# WiFi_Card.net
KiCad netlist of a schematic drawn in Altium Designer
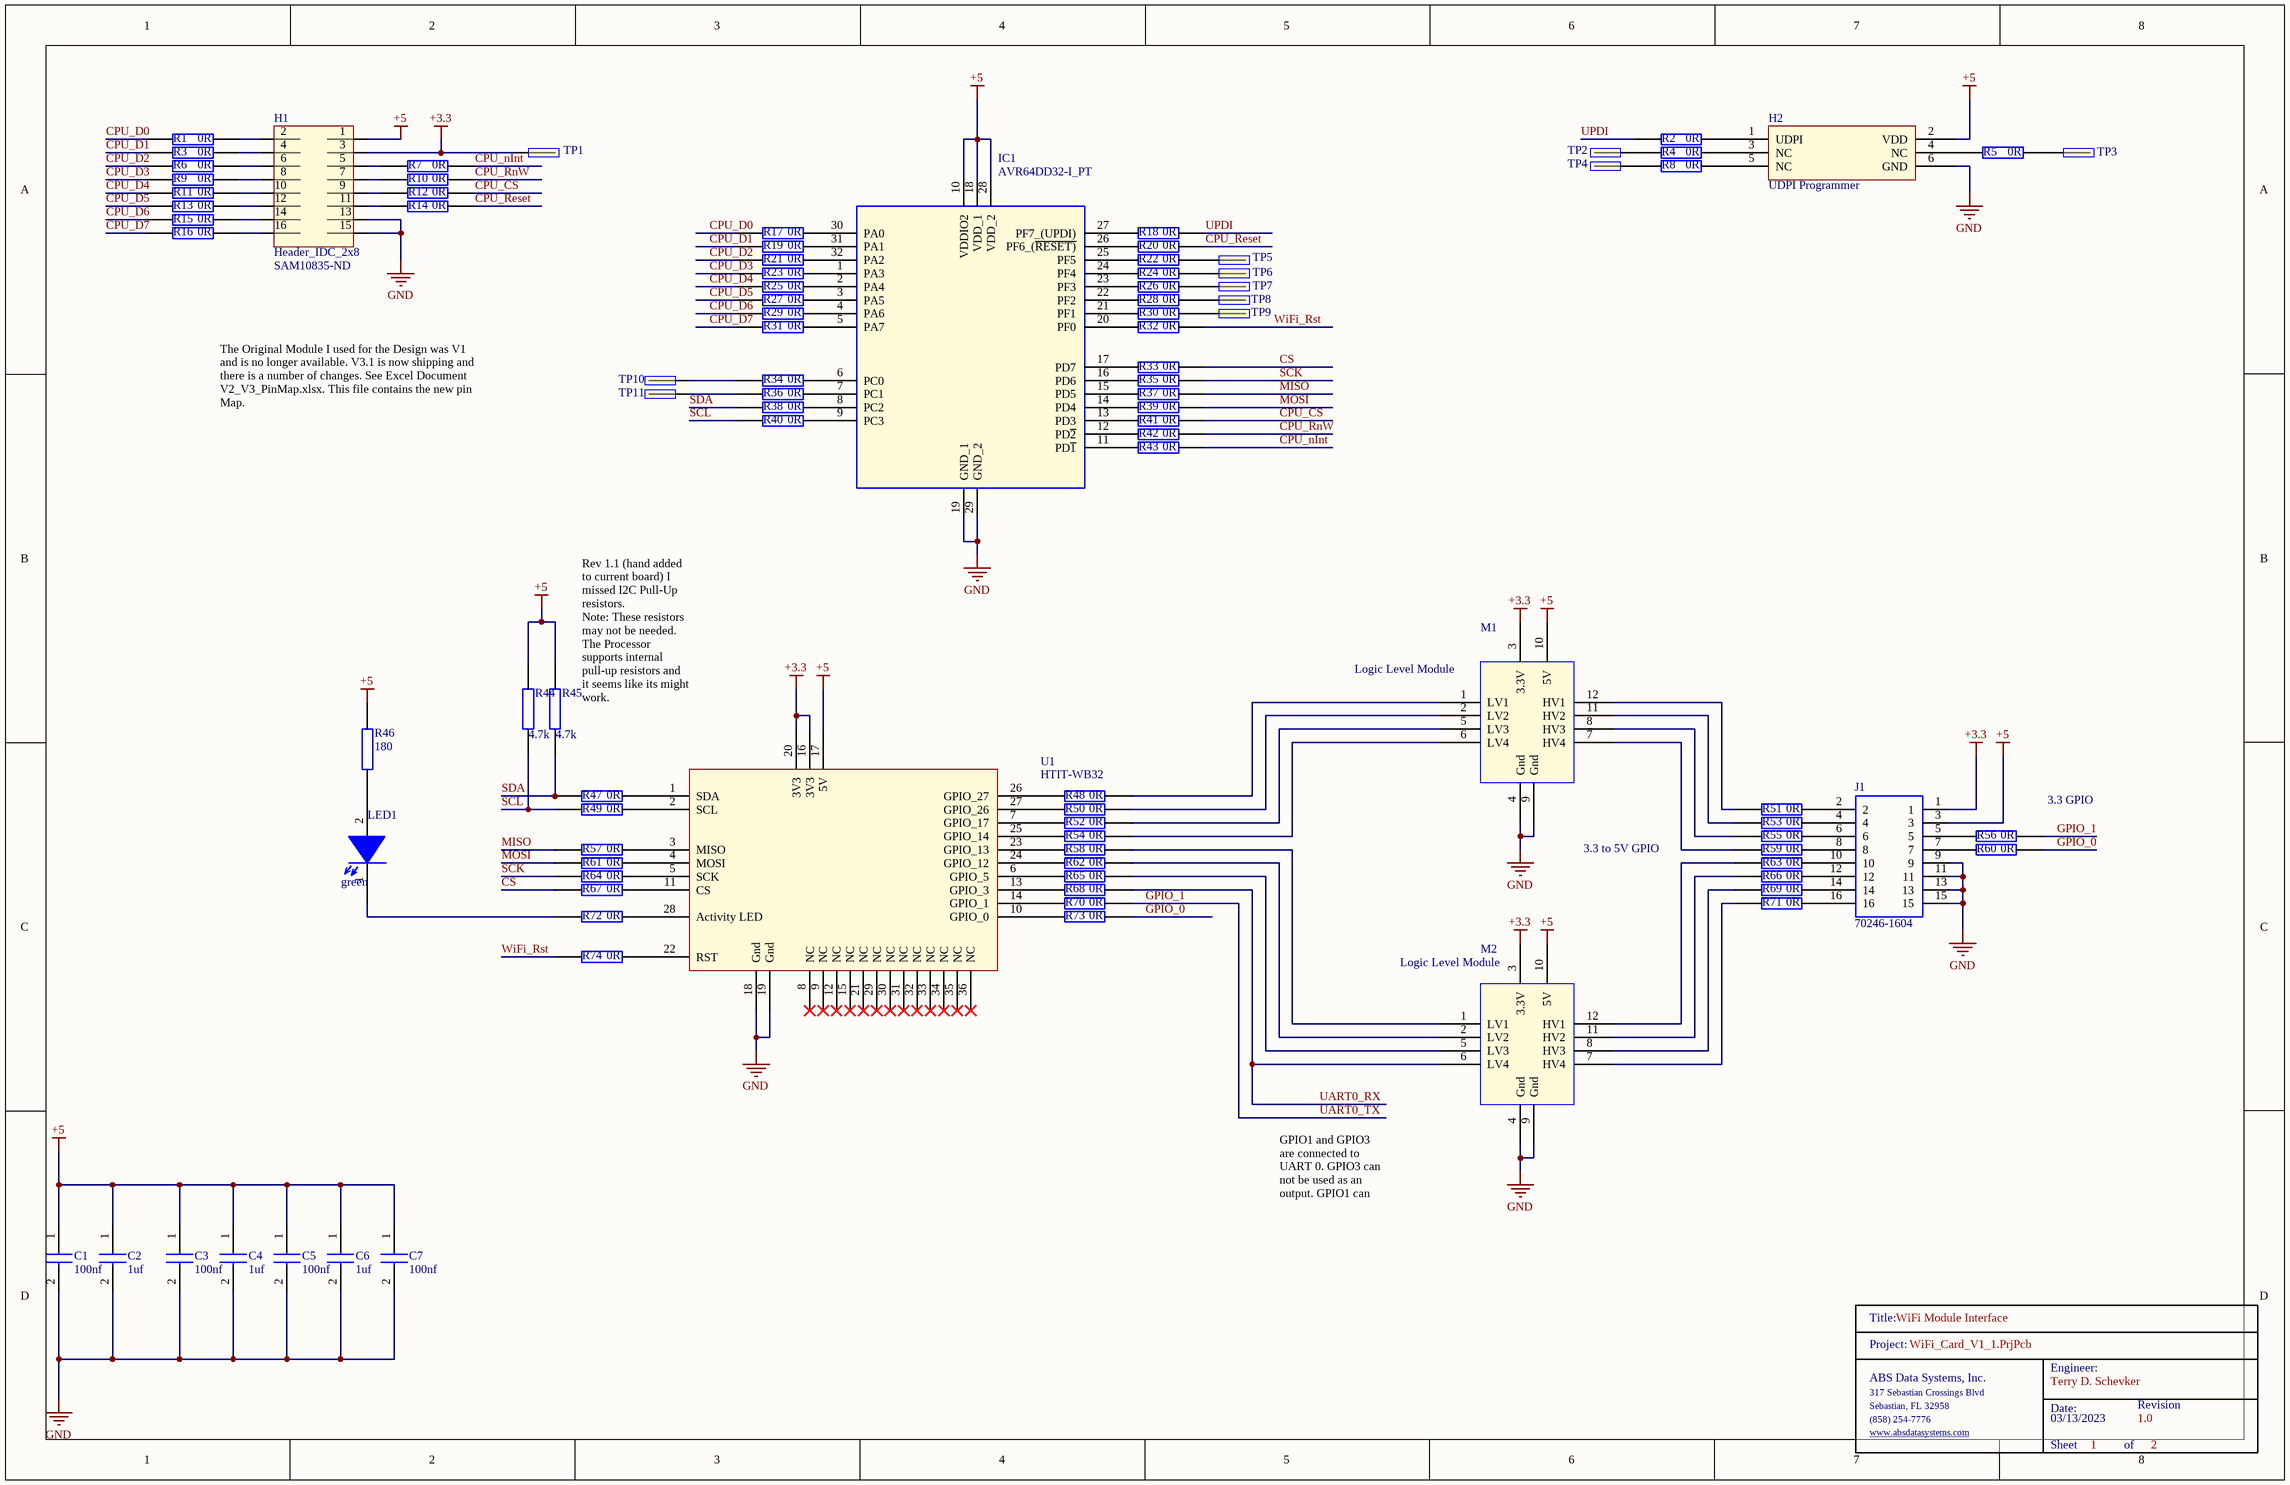
[diagram p0: WiFi_Card.SchDoc]

(export (version "E")
  (design (tool "Eeschema 10.0.6"))
  (components
    (comp (ref "C1")
      (value "100nf")
      (footprint "0603")
      (description "Samsung Electro-Mechanics 0603 100nf")
      (libsource (lib "Capacitors") (part "CL10B104JB8NNNC"))
    )
    (comp (ref "C2")
      (value "1uf")
      (footprint "0603")
      (description "Samsung Electro-Mechanics 0603 1uf")
      (libsource (lib "Capacitors") (part "CL10B105KA8NNNL"))
    )
    (comp (ref "C3")
      (value "100nf")
      (footprint "0603")
      (description "Samsung Electro-Mechanics 0603 100nf")
      (libsource (lib "Capacitors") (part "CL10B104JB8NNNC"))
    )
    (comp (ref "C4")
      (value "1uf")
      (footprint "0603")
      (description "Samsung Electro-Mechanics 0603 1uf")
      (libsource (lib "Capacitors") (part "CL10B105KA8NNNL"))
    )
    (comp (ref "C5")
      (value "100nf")
      (footprint "0603")
      (description "Samsung Electro-Mechanics 0603 100nf")
      (libsource (lib "Capacitors") (part "CL10B104JB8NNNC"))
    )
    (comp (ref "C6")
      (value "1uf")
      (footprint "0603")
      (description "Samsung Electro-Mechanics 0603 1uf")
      (libsource (lib "Capacitors") (part "CL10B105KA8NNNL"))
    )
    (comp (ref "C7")
      (value "100nf")
      (footprint "0603")
      (description "Samsung Electro-Mechanics 0603 100nf")
      (libsource (lib "Capacitors") (part "CL10B104JB8NNNC"))
    )
    (comp (ref "H1")
      (value "Header_IDC_2x8")
      (footprint "HEADER16")
      (description "16 Pin 2x8 Through Hold IDC Connector")
      (fields
        (field (name "MANUFACTURER") "Samtec")
        (field (name "MANUFACTURER PART NUMBER") "TST-108-01-G-D")
        (field (name "SUPPLIER PART NUMBER 1") "SAM10835-ND")
      )
      (libsource (lib "Misc") (part "Header_IDC_2x8"))
    )
    (comp (ref "H2")
      (value "UDPI Programmer")
      (footprint "HDR2X3")
      (description "6 Pin 2X3 Through Hole Header")
      (libsource (lib "Misc") (part "UDPI Programmer"))
    )
    (comp (ref "IC1")
      (value "AVR64DD32-I_PT")
      (footprint "CPU_Memory:QFP80P900X900X120-32N")
      (description "Integrated Circuit")
      (fields (field (name "MANUFACTURER_PART_NUMBER") "AVR64DD32-I/PT ¦ MULTI-VOLTAGE I/O"))
      (libsource (lib "CPU_Memory") (part "AVR64DD32-I_PT"))
    )
    (comp (ref "J1")
      (value "70246-1604")
      (footprint "SHDR16W99P254_2X8_2794X889X927P")
      (description "Molex C-GRID 70246, 2.54mm Pitch, 16 Way, 2 Row, Straight PCB Header, Through Hole")
      (fields (field (name "MOUSER PART NUMBER") "538-70246-1604"))
      (libsource (lib "Connectors") (part "70246-1604"))
    )
    (comp (ref "LED1")
      (value "green")
      (footprint "0603_Diode")
      (description "Wurth Elektronik 0603 green")
      (fields
        (field (name "MANUFACTURER") "Wurth Electronics")
        (field (name "MANUFACTURER PART NUMBER") "150060GS75000")
      )
      (libsource (lib "Misc") (part "150060GS75000"))
    )
    (comp (ref "M1")
      (value "Logic Level Module")
      (footprint "Logic_Level_Module")
      (description "Logic Level Converter Module")
      (libsource (lib "Logic") (part "Logic_Level_Module"))
    )
    (comp (ref "M2")
      (value "Logic Level Module")
      (footprint "Logic_Level_Module")
      (description "Logic Level Converter Module")
      (libsource (lib "Logic") (part "Logic_Level_Module"))
    )
    (comp (ref "R1")
      (value "0R")
      (footprint "0603")
      (description "YAGEO 0603 0 ohm")
      (fields
        (field (name "MOUSER PART NUMBER") "603-RC0603JR-070RL")
        (field (name "MANUFACTURER_PART_NUMBER") "RC0603JR-070RL")
      )
      (libsource (lib "Resistors") (part "RC0603JR-070RL"))
    )
    (comp (ref "R2")
      (value "0R")
      (footprint "0603")
      (description "YAGEO 0603 0 ohm")
      (fields
        (field (name "MOUSER PART NUMBER") "603-RC0603JR-070RL")
        (field (name "MANUFACTURER_PART_NUMBER") "RC0603JR-070RL")
      )
      (libsource (lib "Resistors") (part "RC0603JR-070RL"))
    )
    (comp (ref "R3")
      (value "0R")
      (footprint "0603")
      (description "YAGEO 0603 0 ohm")
      (fields
        (field (name "MOUSER PART NUMBER") "603-RC0603JR-070RL")
        (field (name "MANUFACTURER_PART_NUMBER") "RC0603JR-070RL")
      )
      (libsource (lib "Resistors") (part "RC0603JR-070RL"))
    )
    (comp (ref "R4")
      (value "0R")
      (footprint "0603")
      (description "YAGEO 0603 0 ohm")
      (fields
        (field (name "MOUSER PART NUMBER") "603-RC0603JR-070RL")
        (field (name "MANUFACTURER_PART_NUMBER") "RC0603JR-070RL")
      )
      (libsource (lib "Resistors") (part "RC0603JR-070RL"))
    )
    (comp (ref "R5")
      (value "0R")
      (footprint "0603")
      (description "YAGEO 0603 0 ohm")
      (fields
        (field (name "MOUSER PART NUMBER") "603-RC0603JR-070RL")
        (field (name "MANUFACTURER_PART_NUMBER") "RC0603JR-070RL")
      )
      (libsource (lib "Resistors") (part "RC0603JR-070RL"))
    )
    (comp (ref "R6")
      (value "0R")
      (footprint "0603")
      (description "YAGEO 0603 0 ohm")
      (fields
        (field (name "MOUSER PART NUMBER") "603-RC0603JR-070RL")
        (field (name "MANUFACTURER_PART_NUMBER") "RC0603JR-070RL")
      )
      (libsource (lib "Resistors") (part "RC0603JR-070RL"))
    )
    (comp (ref "R7")
      (value "0R")
      (footprint "0603")
      (description "YAGEO 0603 0 ohm")
      (fields
        (field (name "MOUSER PART NUMBER") "603-RC0603JR-070RL")
        (field (name "MANUFACTURER_PART_NUMBER") "RC0603JR-070RL")
      )
      (libsource (lib "Resistors") (part "RC0603JR-070RL"))
    )
    (comp (ref "R8")
      (value "0R")
      (footprint "0603")
      (description "YAGEO 0603 0 ohm")
      (fields
        (field (name "MOUSER PART NUMBER") "603-RC0603JR-070RL")
        (field (name "MANUFACTURER_PART_NUMBER") "RC0603JR-070RL")
      )
      (libsource (lib "Resistors") (part "RC0603JR-070RL"))
    )
    (comp (ref "R9")
      (value "0R")
      (footprint "0603")
      (description "YAGEO 0603 0 ohm")
      (fields
        (field (name "MOUSER PART NUMBER") "603-RC0603JR-070RL")
        (field (name "MANUFACTURER_PART_NUMBER") "RC0603JR-070RL")
      )
      (libsource (lib "Resistors") (part "RC0603JR-070RL"))
    )
    (comp (ref "R10")
      (value "0R")
      (footprint "0603")
      (description "YAGEO 0603 0 ohm")
      (fields
        (field (name "MOUSER PART NUMBER") "603-RC0603JR-070RL")
        (field (name "MANUFACTURER_PART_NUMBER") "RC0603JR-070RL")
      )
      (libsource (lib "Resistors") (part "RC0603JR-070RL"))
    )
    (comp (ref "R11")
      (value "0R")
      (footprint "0603")
      (description "YAGEO 0603 0 ohm")
      (fields
        (field (name "MOUSER PART NUMBER") "603-RC0603JR-070RL")
        (field (name "MANUFACTURER_PART_NUMBER") "RC0603JR-070RL")
      )
      (libsource (lib "Resistors") (part "RC0603JR-070RL"))
    )
    (comp (ref "R12")
      (value "0R")
      (footprint "0603")
      (description "YAGEO 0603 0 ohm")
      (fields
        (field (name "MOUSER PART NUMBER") "603-RC0603JR-070RL")
        (field (name "MANUFACTURER_PART_NUMBER") "RC0603JR-070RL")
      )
      (libsource (lib "Resistors") (part "RC0603JR-070RL"))
    )
    (comp (ref "R13")
      (value "0R")
      (footprint "0603")
      (description "YAGEO 0603 0 ohm")
      (fields
        (field (name "MOUSER PART NUMBER") "603-RC0603JR-070RL")
        (field (name "MANUFACTURER_PART_NUMBER") "RC0603JR-070RL")
      )
      (libsource (lib "Resistors") (part "RC0603JR-070RL"))
    )
    (comp (ref "R14")
      (value "0R")
      (footprint "0603")
      (description "YAGEO 0603 0 ohm")
      (fields
        (field (name "MOUSER PART NUMBER") "603-RC0603JR-070RL")
        (field (name "MANUFACTURER_PART_NUMBER") "RC0603JR-070RL")
      )
      (libsource (lib "Resistors") (part "RC0603JR-070RL"))
    )
    (comp (ref "R15")
      (value "0R")
      (footprint "0603")
      (description "YAGEO 0603 0 ohm")
      (fields
        (field (name "MOUSER PART NUMBER") "603-RC0603JR-070RL")
        (field (name "MANUFACTURER_PART_NUMBER") "RC0603JR-070RL")
      )
      (libsource (lib "Resistors") (part "RC0603JR-070RL"))
    )
    (comp (ref "R16")
      (value "0R")
      (footprint "0603")
      (description "YAGEO 0603 0 ohm")
      (fields
        (field (name "MOUSER PART NUMBER") "603-RC0603JR-070RL")
        (field (name "MANUFACTURER_PART_NUMBER") "RC0603JR-070RL")
      )
      (libsource (lib "Resistors") (part "RC0603JR-070RL"))
    )
    (comp (ref "R17")
      (value "0R")
      (footprint "0603")
      (description "YAGEO 0603 0 ohm")
      (fields
        (field (name "MOUSER PART NUMBER") "603-RC0603JR-070RL")
        (field (name "MANUFACTURER_PART_NUMBER") "RC0603JR-070RL")
      )
      (libsource (lib "Resistors") (part "RC0603JR-070RL"))
    )
    (comp (ref "R18")
      (value "0R")
      (footprint "0603")
      (description "YAGEO 0603 0 ohm")
      (fields
        (field (name "MOUSER PART NUMBER") "603-RC0603JR-070RL")
        (field (name "MANUFACTURER_PART_NUMBER") "RC0603JR-070RL")
      )
      (libsource (lib "Resistors") (part "RC0603JR-070RL"))
    )
    (comp (ref "R19")
      (value "0R")
      (footprint "0603")
      (description "YAGEO 0603 0 ohm")
      (fields
        (field (name "MOUSER PART NUMBER") "603-RC0603JR-070RL")
        (field (name "MANUFACTURER_PART_NUMBER") "RC0603JR-070RL")
      )
      (libsource (lib "Resistors") (part "RC0603JR-070RL"))
    )
    (comp (ref "R20")
      (value "0R")
      (footprint "0603")
      (description "YAGEO 0603 0 ohm")
      (fields
        (field (name "MOUSER PART NUMBER") "603-RC0603JR-070RL")
        (field (name "MANUFACTURER_PART_NUMBER") "RC0603JR-070RL")
      )
      (libsource (lib "Resistors") (part "RC0603JR-070RL"))
    )
    (comp (ref "R21")
      (value "0R")
      (footprint "0603")
      (description "YAGEO 0603 0 ohm")
      (fields
        (field (name "MOUSER PART NUMBER") "603-RC0603JR-070RL")
        (field (name "MANUFACTURER_PART_NUMBER") "RC0603JR-070RL")
      )
      (libsource (lib "Resistors") (part "RC0603JR-070RL"))
    )
    (comp (ref "R22")
      (value "0R")
      (footprint "0603")
      (description "YAGEO 0603 0 ohm")
      (fields
        (field (name "MOUSER PART NUMBER") "603-RC0603JR-070RL")
        (field (name "MANUFACTURER_PART_NUMBER") "RC0603JR-070RL")
      )
      (libsource (lib "Resistors") (part "RC0603JR-070RL"))
    )
    (comp (ref "R23")
      (value "0R")
      (footprint "0603")
      (description "YAGEO 0603 0 ohm")
      (fields
        (field (name "MOUSER PART NUMBER") "603-RC0603JR-070RL")
        (field (name "MANUFACTURER_PART_NUMBER") "RC0603JR-070RL")
      )
      (libsource (lib "Resistors") (part "RC0603JR-070RL"))
    )
    (comp (ref "R24")
      (value "0R")
      (footprint "0603")
      (description "YAGEO 0603 0 ohm")
      (fields
        (field (name "MOUSER PART NUMBER") "603-RC0603JR-070RL")
        (field (name "MANUFACTURER_PART_NUMBER") "RC0603JR-070RL")
      )
      (libsource (lib "Resistors") (part "RC0603JR-070RL"))
    )
    (comp (ref "R25")
      (value "0R")
      (footprint "0603")
      (description "YAGEO 0603 0 ohm")
      (fields
        (field (name "MOUSER PART NUMBER") "603-RC0603JR-070RL")
        (field (name "MANUFACTURER_PART_NUMBER") "RC0603JR-070RL")
      )
      (libsource (lib "Resistors") (part "RC0603JR-070RL"))
    )
    (comp (ref "R26")
      (value "0R")
      (footprint "0603")
      (description "YAGEO 0603 0 ohm")
      (fields
        (field (name "MOUSER PART NUMBER") "603-RC0603JR-070RL")
        (field (name "MANUFACTURER_PART_NUMBER") "RC0603JR-070RL")
      )
      (libsource (lib "Resistors") (part "RC0603JR-070RL"))
    )
    (comp (ref "R27")
      (value "0R")
      (footprint "0603")
      (description "YAGEO 0603 0 ohm")
      (fields
        (field (name "MOUSER PART NUMBER") "603-RC0603JR-070RL")
        (field (name "MANUFACTURER_PART_NUMBER") "RC0603JR-070RL")
      )
      (libsource (lib "Resistors") (part "RC0603JR-070RL"))
    )
    (comp (ref "R28")
      (value "0R")
      (footprint "0603")
      (description "YAGEO 0603 0 ohm")
      (fields
        (field (name "MOUSER PART NUMBER") "603-RC0603JR-070RL")
        (field (name "MANUFACTURER_PART_NUMBER") "RC0603JR-070RL")
      )
      (libsource (lib "Resistors") (part "RC0603JR-070RL"))
    )
    (comp (ref "R29")
      (value "0R")
      (footprint "0603")
      (description "YAGEO 0603 0 ohm")
      (fields
        (field (name "MOUSER PART NUMBER") "603-RC0603JR-070RL")
        (field (name "MANUFACTURER_PART_NUMBER") "RC0603JR-070RL")
      )
      (libsource (lib "Resistors") (part "RC0603JR-070RL"))
    )
    (comp (ref "R30")
      (value "0R")
      (footprint "0603")
      (description "YAGEO 0603 0 ohm")
      (fields
        (field (name "MOUSER PART NUMBER") "603-RC0603JR-070RL")
        (field (name "MANUFACTURER_PART_NUMBER") "RC0603JR-070RL")
      )
      (libsource (lib "Resistors") (part "RC0603JR-070RL"))
    )
    (comp (ref "R31")
      (value "0R")
      (footprint "0603")
      (description "YAGEO 0603 0 ohm")
      (fields
        (field (name "MOUSER PART NUMBER") "603-RC0603JR-070RL")
        (field (name "MANUFACTURER_PART_NUMBER") "RC0603JR-070RL")
      )
      (libsource (lib "Resistors") (part "RC0603JR-070RL"))
    )
    (comp (ref "R32")
      (value "0R")
      (footprint "0603")
      (description "YAGEO 0603 0 ohm")
      (fields
        (field (name "MOUSER PART NUMBER") "603-RC0603JR-070RL")
        (field (name "MANUFACTURER_PART_NUMBER") "RC0603JR-070RL")
      )
      (libsource (lib "Resistors") (part "RC0603JR-070RL"))
    )
    (comp (ref "R33")
      (value "0R")
      (footprint "0603")
      (description "YAGEO 0603 0 ohm")
      (fields
        (field (name "MOUSER PART NUMBER") "603-RC0603JR-070RL")
        (field (name "MANUFACTURER_PART_NUMBER") "RC0603JR-070RL")
      )
      (libsource (lib "Resistors") (part "RC0603JR-070RL"))
    )
    (comp (ref "R34")
      (value "0R")
      (footprint "0603")
      (description "YAGEO 0603 0 ohm")
      (fields
        (field (name "MOUSER PART NUMBER") "603-RC0603JR-070RL")
        (field (name "MANUFACTURER_PART_NUMBER") "RC0603JR-070RL")
      )
      (libsource (lib "Resistors") (part "RC0603JR-070RL"))
    )
    (comp (ref "R35")
      (value "0R")
      (footprint "0603")
      (description "YAGEO 0603 0 ohm")
      (fields
        (field (name "MOUSER PART NUMBER") "603-RC0603JR-070RL")
        (field (name "MANUFACTURER_PART_NUMBER") "RC0603JR-070RL")
      )
      (libsource (lib "Resistors") (part "RC0603JR-070RL"))
    )
    (comp (ref "R36")
      (value "0R")
      (footprint "0603")
      (description "YAGEO 0603 0 ohm")
      (fields
        (field (name "MOUSER PART NUMBER") "603-RC0603JR-070RL")
        (field (name "MANUFACTURER_PART_NUMBER") "RC0603JR-070RL")
      )
      (libsource (lib "Resistors") (part "RC0603JR-070RL"))
    )
    (comp (ref "R37")
      (value "0R")
      (footprint "0603")
      (description "YAGEO 0603 0 ohm")
      (fields
        (field (name "MOUSER PART NUMBER") "603-RC0603JR-070RL")
        (field (name "MANUFACTURER_PART_NUMBER") "RC0603JR-070RL")
      )
      (libsource (lib "Resistors") (part "RC0603JR-070RL"))
    )
    (comp (ref "R38")
      (value "0R")
      (footprint "0603")
      (description "YAGEO 0603 0 ohm")
      (fields
        (field (name "MOUSER PART NUMBER") "603-RC0603JR-070RL")
        (field (name "MANUFACTURER_PART_NUMBER") "RC0603JR-070RL")
      )
      (libsource (lib "Resistors") (part "RC0603JR-070RL"))
    )
    (comp (ref "R39")
      (value "0R")
      (footprint "0603")
      (description "YAGEO 0603 0 ohm")
      (fields
        (field (name "MOUSER PART NUMBER") "603-RC0603JR-070RL")
        (field (name "MANUFACTURER_PART_NUMBER") "RC0603JR-070RL")
      )
      (libsource (lib "Resistors") (part "RC0603JR-070RL"))
    )
    (comp (ref "R40")
      (value "0R")
      (footprint "0603")
      (description "YAGEO 0603 0 ohm")
      (fields
        (field (name "MOUSER PART NUMBER") "603-RC0603JR-070RL")
        (field (name "MANUFACTURER_PART_NUMBER") "RC0603JR-070RL")
      )
      (libsource (lib "Resistors") (part "RC0603JR-070RL"))
    )
    (comp (ref "R41")
      (value "0R")
      (footprint "0603")
      (description "YAGEO 0603 0 ohm")
      (fields
        (field (name "MOUSER PART NUMBER") "603-RC0603JR-070RL")
        (field (name "MANUFACTURER_PART_NUMBER") "RC0603JR-070RL")
      )
      (libsource (lib "Resistors") (part "RC0603JR-070RL"))
    )
    (comp (ref "R42")
      (value "0R")
      (footprint "0603")
      (description "YAGEO 0603 0 ohm")
      (fields
        (field (name "MOUSER PART NUMBER") "603-RC0603JR-070RL")
        (field (name "MANUFACTURER_PART_NUMBER") "RC0603JR-070RL")
      )
      (libsource (lib "Resistors") (part "RC0603JR-070RL"))
    )
    (comp (ref "R43")
      (value "0R")
      (footprint "0603")
      (description "YAGEO 0603 0 ohm")
      (fields
        (field (name "MOUSER PART NUMBER") "603-RC0603JR-070RL")
        (field (name "MANUFACTURER_PART_NUMBER") "RC0603JR-070RL")
      )
      (libsource (lib "Resistors") (part "RC0603JR-070RL"))
    )
    (comp (ref "R44")
      (value "4.7k")
      (footprint "Capacitors:0603")
      (description "YAGEO 0603 4.7k")
      (fields
        (field (name "MOUSER PART NUMBER") "603-RC0603JR-070RL")
        (field (name "MANUFACTURER_PART_NUMBER") "RC0603JR-070RL")
      )
      (libsource (lib "Resistors") (part "RC0603FR-104K7L"))
    )
    (comp (ref "R45")
      (value "4.7k")
      (footprint "Capacitors:0603")
      (description "YAGEO 0603 4.7k")
      (fields
        (field (name "MOUSER PART NUMBER") "603-RC0603JR-070RL")
        (field (name "MANUFACTURER_PART_NUMBER") "RC0603JR-070RL")
      )
      (libsource (lib "Resistors") (part "RC0603FR-104K7L"))
    )
    (comp (ref "R46")
      (value "180")
      (footprint "0603")
      (description "YAGEO 0603 180 ohm")
      (fields
        (field (name "MOUSER PART NUMBER") "603-RC0603JR-070RL")
        (field (name "MANUFACTURER_PART_NUMBER") "RC0603JR-070RL")
      )
      (libsource (lib "Resistors") (part "RC0603FR-13180RL"))
    )
    (comp (ref "R47")
      (value "0R")
      (footprint "0603")
      (description "YAGEO 0603 0 ohm")
      (fields
        (field (name "MOUSER PART NUMBER") "603-RC0603JR-070RL")
        (field (name "MANUFACTURER_PART_NUMBER") "RC0603JR-070RL")
      )
      (libsource (lib "Resistors") (part "RC0603JR-070RL"))
    )
    (comp (ref "R48")
      (value "0R")
      (footprint "0603")
      (description "YAGEO 0603 0 ohm")
      (fields
        (field (name "MOUSER PART NUMBER") "603-RC0603JR-070RL")
        (field (name "MANUFACTURER_PART_NUMBER") "RC0603JR-070RL")
      )
      (libsource (lib "Resistors") (part "RC0603JR-070RL"))
    )
    (comp (ref "R49")
      (value "0R")
      (footprint "0603")
      (description "YAGEO 0603 0 ohm")
      (fields
        (field (name "MOUSER PART NUMBER") "603-RC0603JR-070RL")
        (field (name "MANUFACTURER_PART_NUMBER") "RC0603JR-070RL")
      )
      (libsource (lib "Resistors") (part "RC0603JR-070RL"))
    )
    (comp (ref "R50")
      (value "0R")
      (footprint "0603")
      (description "YAGEO 0603 0 ohm")
      (fields
        (field (name "MOUSER PART NUMBER") "603-RC0603JR-070RL")
        (field (name "MANUFACTURER_PART_NUMBER") "RC0603JR-070RL")
      )
      (libsource (lib "Resistors") (part "RC0603JR-070RL"))
    )
    (comp (ref "R51")
      (value "0R")
      (footprint "0603")
      (description "YAGEO 0603 0 ohm")
      (fields
        (field (name "MOUSER PART NUMBER") "603-RC0603JR-070RL")
        (field (name "MANUFACTURER_PART_NUMBER") "RC0603JR-070RL")
      )
      (libsource (lib "Resistors") (part "RC0603JR-070RL"))
    )
    (comp (ref "R52")
      (value "0R")
      (footprint "0603")
      (description "YAGEO 0603 0 ohm")
      (fields
        (field (name "MOUSER PART NUMBER") "603-RC0603JR-070RL")
        (field (name "MANUFACTURER_PART_NUMBER") "RC0603JR-070RL")
      )
      (libsource (lib "Resistors") (part "RC0603JR-070RL"))
    )
    (comp (ref "R53")
      (value "0R")
      (footprint "0603")
      (description "YAGEO 0603 0 ohm")
      (fields
        (field (name "MOUSER PART NUMBER") "603-RC0603JR-070RL")
        (field (name "MANUFACTURER_PART_NUMBER") "RC0603JR-070RL")
      )
      (libsource (lib "Resistors") (part "RC0603JR-070RL"))
    )
    (comp (ref "R54")
      (value "0R")
      (footprint "0603")
      (description "YAGEO 0603 0 ohm")
      (fields
        (field (name "MOUSER PART NUMBER") "603-RC0603JR-070RL")
        (field (name "MANUFACTURER_PART_NUMBER") "RC0603JR-070RL")
      )
      (libsource (lib "Resistors") (part "RC0603JR-070RL"))
    )
    (comp (ref "R55")
      (value "0R")
      (footprint "0603")
      (description "YAGEO 0603 0 ohm")
      (fields
        (field (name "MOUSER PART NUMBER") "603-RC0603JR-070RL")
        (field (name "MANUFACTURER_PART_NUMBER") "RC0603JR-070RL")
      )
      (libsource (lib "Resistors") (part "RC0603JR-070RL"))
    )
    (comp (ref "R56")
      (value "0R")
      (footprint "0603")
      (description "YAGEO 0603 0 ohm")
      (fields
        (field (name "MOUSER PART NUMBER") "603-RC0603JR-070RL")
        (field (name "MANUFACTURER_PART_NUMBER") "RC0603JR-070RL")
      )
      (libsource (lib "Resistors") (part "RC0603JR-070RL"))
    )
    (comp (ref "R57")
      (value "0R")
      (footprint "0603")
      (description "YAGEO 0603 0 ohm")
      (fields
        (field (name "MOUSER PART NUMBER") "603-RC0603JR-070RL")
        (field (name "MANUFACTURER_PART_NUMBER") "RC0603JR-070RL")
      )
      (libsource (lib "Resistors") (part "RC0603JR-070RL"))
    )
    (comp (ref "R58")
      (value "0R")
      (footprint "0603")
      (description "YAGEO 0603 0 ohm")
      (fields
        (field (name "MOUSER PART NUMBER") "603-RC0603JR-070RL")
        (field (name "MANUFACTURER_PART_NUMBER") "RC0603JR-070RL")
      )
      (libsource (lib "Resistors") (part "RC0603JR-070RL"))
    )
    (comp (ref "R59")
      (value "0R")
      (footprint "0603")
      (description "YAGEO 0603 0 ohm")
      (fields
        (field (name "MOUSER PART NUMBER") "603-RC0603JR-070RL")
        (field (name "MANUFACTURER_PART_NUMBER") "RC0603JR-070RL")
      )
      (libsource (lib "Resistors") (part "RC0603JR-070RL"))
    )
    (comp (ref "R60")
      (value "0R")
      (footprint "0603")
      (description "YAGEO 0603 0 ohm")
      (fields
        (field (name "MOUSER PART NUMBER") "603-RC0603JR-070RL")
        (field (name "MANUFACTURER_PART_NUMBER") "RC0603JR-070RL")
      )
      (libsource (lib "Resistors") (part "RC0603JR-070RL"))
    )
    (comp (ref "R61")
      (value "0R")
      (footprint "0603")
      (description "YAGEO 0603 0 ohm")
      (fields
        (field (name "MOUSER PART NUMBER") "603-RC0603JR-070RL")
        (field (name "MANUFACTURER_PART_NUMBER") "RC0603JR-070RL")
      )
      (libsource (lib "Resistors") (part "RC0603JR-070RL"))
    )
    (comp (ref "R62")
      (value "0R")
      (footprint "0603")
      (description "YAGEO 0603 0 ohm")
      (fields
        (field (name "MOUSER PART NUMBER") "603-RC0603JR-070RL")
        (field (name "MANUFACTURER_PART_NUMBER") "RC0603JR-070RL")
      )
      (libsource (lib "Resistors") (part "RC0603JR-070RL"))
    )
    (comp (ref "R63")
      (value "0R")
      (footprint "0603")
      (description "YAGEO 0603 0 ohm")
      (fields
        (field (name "MOUSER PART NUMBER") "603-RC0603JR-070RL")
        (field (name "MANUFACTURER_PART_NUMBER") "RC0603JR-070RL")
      )
      (libsource (lib "Resistors") (part "RC0603JR-070RL"))
    )
    (comp (ref "R64")
      (value "0R")
      (footprint "0603")
      (description "YAGEO 0603 0 ohm")
      (fields
        (field (name "MOUSER PART NUMBER") "603-RC0603JR-070RL")
        (field (name "MANUFACTURER_PART_NUMBER") "RC0603JR-070RL")
      )
      (libsource (lib "Resistors") (part "RC0603JR-070RL"))
    )
    (comp (ref "R65")
      (value "0R")
      (footprint "0603")
      (description "YAGEO 0603 0 ohm")
      (fields
        (field (name "MOUSER PART NUMBER") "603-RC0603JR-070RL")
        (field (name "MANUFACTURER_PART_NUMBER") "RC0603JR-070RL")
      )
      (libsource (lib "Resistors") (part "RC0603JR-070RL"))
    )
    (comp (ref "R66")
      (value "0R")
      (footprint "0603")
      (description "YAGEO 0603 0 ohm")
      (fields
        (field (name "MOUSER PART NUMBER") "603-RC0603JR-070RL")
        (field (name "MANUFACTURER_PART_NUMBER") "RC0603JR-070RL")
      )
      (libsource (lib "Resistors") (part "RC0603JR-070RL"))
    )
    (comp (ref "R67")
      (value "0R")
      (footprint "0603")
      (description "YAGEO 0603 0 ohm")
      (fields
        (field (name "MOUSER PART NUMBER") "603-RC0603JR-070RL")
        (field (name "MANUFACTURER_PART_NUMBER") "RC0603JR-070RL")
      )
      (libsource (lib "Resistors") (part "RC0603JR-070RL"))
    )
    (comp (ref "R68")
      (value "0R")
      (footprint "0603")
      (description "YAGEO 0603 0 ohm")
      (fields
        (field (name "MOUSER PART NUMBER") "603-RC0603JR-070RL")
        (field (name "MANUFACTURER_PART_NUMBER") "RC0603JR-070RL")
      )
      (libsource (lib "Resistors") (part "RC0603JR-070RL"))
    )
    (comp (ref "R69")
      (value "0R")
      (footprint "0603")
      (description "YAGEO 0603 0 ohm")
      (fields
        (field (name "MOUSER PART NUMBER") "603-RC0603JR-070RL")
        (field (name "MANUFACTURER_PART_NUMBER") "RC0603JR-070RL")
      )
      (libsource (lib "Resistors") (part "RC0603JR-070RL"))
    )
    (comp (ref "R70")
      (value "0R")
      (footprint "0603")
      (description "YAGEO 0603 0 ohm")
      (fields
        (field (name "MOUSER PART NUMBER") "603-RC0603JR-070RL")
        (field (name "MANUFACTURER_PART_NUMBER") "RC0603JR-070RL")
      )
      (libsource (lib "Resistors") (part "RC0603JR-070RL"))
    )
    (comp (ref "R71")
      (value "0R")
      (footprint "0603")
      (description "YAGEO 0603 0 ohm")
      (fields
        (field (name "MOUSER PART NUMBER") "603-RC0603JR-070RL")
        (field (name "MANUFACTURER_PART_NUMBER") "RC0603JR-070RL")
      )
      (libsource (lib "Resistors") (part "RC0603JR-070RL"))
    )
    (comp (ref "R72")
      (value "0R")
      (footprint "0603")
      (description "YAGEO 0603 0 ohm")
      (fields
        (field (name "MOUSER PART NUMBER") "603-RC0603JR-070RL")
        (field (name "MANUFACTURER_PART_NUMBER") "RC0603JR-070RL")
      )
      (libsource (lib "Resistors") (part "RC0603JR-070RL"))
    )
    (comp (ref "R73")
      (value "0R")
      (footprint "0603")
      (description "YAGEO 0603 0 ohm")
      (fields
        (field (name "MOUSER PART NUMBER") "603-RC0603JR-070RL")
        (field (name "MANUFACTURER_PART_NUMBER") "RC0603JR-070RL")
      )
      (libsource (lib "Resistors") (part "RC0603JR-070RL"))
    )
    (comp (ref "R74")
      (value "0R")
      (footprint "0603")
      (description "YAGEO 0603 0 ohm")
      (fields
        (field (name "MOUSER PART NUMBER") "603-RC0603JR-070RL")
        (field (name "MANUFACTURER_PART_NUMBER") "RC0603JR-070RL")
      )
      (libsource (lib "Resistors") (part "RC0603JR-070RL"))
    )
    (comp (ref "TitleBlock_1") (value "TitleBlock") (libsource (lib "Misc") (part "TitleBlock")))
    (comp (ref "TP1")
      (value "TP")
      (footprint "TP")
      (fields
        (field (name "MANUFACTURER") "Samtec")
        (field (name "MANUFACTURER PART NUMBER") "TST-105-01-G-D")
      )
      (libsource (lib "Misc") (part "TP"))
    )
    (comp (ref "TP2")
      (value "TP")
      (footprint "TP")
      (fields
        (field (name "MANUFACTURER") "Samtec")
        (field (name "MANUFACTURER PART NUMBER") "TST-105-01-G-D")
      )
      (libsource (lib "") (part "TP_1"))
    )
    (comp (ref "TP3")
      (value "TP")
      (footprint "TP")
      (fields
        (field (name "MANUFACTURER") "Samtec")
        (field (name "MANUFACTURER PART NUMBER") "TST-105-01-G-D")
      )
      (libsource (lib "Misc") (part "TP"))
    )
    (comp (ref "TP4")
      (value "TP")
      (footprint "TP")
      (fields
        (field (name "MANUFACTURER") "Samtec")
        (field (name "MANUFACTURER PART NUMBER") "TST-105-01-G-D")
      )
      (libsource (lib "") (part "TP_1"))
    )
    (comp (ref "TP5")
      (value "TP")
      (footprint "TP")
      (fields
        (field (name "MANUFACTURER") "Samtec")
        (field (name "MANUFACTURER PART NUMBER") "TST-105-01-G-D")
      )
      (libsource (lib "Misc") (part "TP"))
    )
    (comp (ref "TP6")
      (value "TP")
      (footprint "TP")
      (fields
        (field (name "MANUFACTURER") "Samtec")
        (field (name "MANUFACTURER PART NUMBER") "TST-105-01-G-D")
      )
      (libsource (lib "Misc") (part "TP"))
    )
    (comp (ref "TP7")
      (value "TP")
      (footprint "TP")
      (fields
        (field (name "MANUFACTURER") "Samtec")
        (field (name "MANUFACTURER PART NUMBER") "TST-105-01-G-D")
      )
      (libsource (lib "Misc") (part "TP"))
    )
    (comp (ref "TP8")
      (value "TP")
      (footprint "TP")
      (fields
        (field (name "MANUFACTURER") "Samtec")
        (field (name "MANUFACTURER PART NUMBER") "TST-105-01-G-D")
      )
      (libsource (lib "Misc") (part "TP"))
    )
    (comp (ref "TP9")
      (value "TP")
      (footprint "TP")
      (fields
        (field (name "MANUFACTURER") "Samtec")
        (field (name "MANUFACTURER PART NUMBER") "TST-105-01-G-D")
      )
      (libsource (lib "Misc") (part "TP"))
    )
    (comp (ref "TP10")
      (value "TP")
      (footprint "TP")
      (fields
        (field (name "MANUFACTURER") "Samtec")
        (field (name "MANUFACTURER PART NUMBER") "TST-105-01-G-D")
      )
      (libsource (lib "") (part "TP_1"))
    )
    (comp (ref "TP11")
      (value "TP")
      (footprint "TP")
      (fields
        (field (name "MANUFACTURER") "Samtec")
        (field (name "MANUFACTURER PART NUMBER") "TST-105-01-G-D")
      )
      (libsource (lib "") (part "TP_1"))
    )
    (comp (ref "U1")
      (value "HTIT-WB32")
      (footprint "DIP36Wide")
      (description "WIFI Module")
      (libsource (lib "Misc") (part "HTIT-WB32"))
    )
  )
  (nets
    (net (code "1") (name "+3.3") (class "Default")
      (node (ref "H1") (pin "3") (pinfunction "3_3") (pintype "passive"))
      (node (ref "J1") (pin "1") (pinfunction "1_1") (pintype "passive"))
      (node (ref "M1") (pin "3") (pinfunction "3.3V_3") (pintype "passive"))
      (node (ref "M2") (pin "3") (pinfunction "3.3V_3") (pintype "passive"))
      (node (ref "TP1") (pin "1") (pinfunction "1_1") (pintype "passive"))
      (node (ref "U1") (pin "16") (pinfunction "3V3_16") (pintype "passive"))
      (node (ref "U1") (pin "20") (pinfunction "3V3_20") (pintype "passive"))
    )
    (net (code "2") (name "+5") (class "Default")
      (node (ref "C1") (pin "1") (pinfunction "1_1") (pintype "passive"))
      (node (ref "C2") (pin "1") (pinfunction "1_1") (pintype "passive"))
      (node (ref "C3") (pin "1") (pinfunction "1_1") (pintype "passive"))
      (node (ref "C4") (pin "1") (pinfunction "1_1") (pintype "passive"))
      (node (ref "C5") (pin "1") (pinfunction "1_1") (pintype "passive"))
      (node (ref "C6") (pin "1") (pinfunction "1_1") (pintype "passive"))
      (node (ref "C7") (pin "1") (pinfunction "1_1") (pintype "passive"))
      (node (ref "H1") (pin "1") (pinfunction "1_1") (pintype "passive"))
      (node (ref "H2") (pin "2") (pinfunction "VDD_2") (pintype "passive"))
      (node (ref "IC1") (pin "10") (pinfunction "VDDIO2_10") (pintype "passive"))
      (node (ref "IC1") (pin "18") (pinfunction "VDD_1_18") (pintype "passive"))
      (node (ref "IC1") (pin "28") (pinfunction "VDD_2_28") (pintype "passive"))
      (node (ref "J1") (pin "3") (pinfunction "3_3") (pintype "passive"))
      (node (ref "M1") (pin "10") (pinfunction "5V_10") (pintype "passive"))
      (node (ref "M2") (pin "10") (pinfunction "5V_10") (pintype "passive"))
      (node (ref "R44") (pin "2") (pinfunction "2_2") (pintype "passive"))
      (node (ref "R45") (pin "2") (pinfunction "2_2") (pintype "passive"))
      (node (ref "R46") (pin "2") (pinfunction "2_2") (pintype "passive"))
      (node (ref "U1") (pin "17") (pinfunction "5V_17") (pintype "passive"))
    )
    (net (code "3") (name "/CPU_CS") (class "Default")
      (node (ref "R12") (pin "2") (pinfunction "2_2") (pintype "passive"))
      (node (ref "R41") (pin "2") (pinfunction "2_2") (pintype "passive"))
    )
    (net (code "4") (name "/CPU_D0") (class "Default")
      (node (ref "R1") (pin "1") (pinfunction "1_1") (pintype "passive"))
      (node (ref "R17") (pin "1") (pinfunction "1_1") (pintype "passive"))
    )
    (net (code "5") (name "/CPU_D1") (class "Default")
      (node (ref "R19") (pin "1") (pinfunction "1_1") (pintype "passive"))
      (node (ref "R3") (pin "1") (pinfunction "1_1") (pintype "passive"))
    )
    (net (code "6") (name "/CPU_D2") (class "Default")
      (node (ref "R21") (pin "1") (pinfunction "1_1") (pintype "passive"))
      (node (ref "R6") (pin "1") (pinfunction "1_1") (pintype "passive"))
    )
    (net (code "7") (name "/CPU_D3") (class "Default")
      (node (ref "R23") (pin "1") (pinfunction "1_1") (pintype "passive"))
      (node (ref "R9") (pin "1") (pinfunction "1_1") (pintype "passive"))
    )
    (net (code "8") (name "/CPU_D4") (class "Default")
      (node (ref "R11") (pin "1") (pinfunction "1_1") (pintype "passive"))
      (node (ref "R25") (pin "1") (pinfunction "1_1") (pintype "passive"))
    )
    (net (code "9") (name "/CPU_D5") (class "Default")
      (node (ref "R13") (pin "1") (pinfunction "1_1") (pintype "passive"))
      (node (ref "R27") (pin "1") (pinfunction "1_1") (pintype "passive"))
    )
    (net (code "10") (name "/CPU_D6") (class "Default")
      (node (ref "R15") (pin "1") (pinfunction "1_1") (pintype "passive"))
      (node (ref "R29") (pin "1") (pinfunction "1_1") (pintype "passive"))
    )
    (net (code "11") (name "/CPU_D7") (class "Default")
      (node (ref "R16") (pin "1") (pinfunction "1_1") (pintype "passive"))
      (node (ref "R31") (pin "1") (pinfunction "1_1") (pintype "passive"))
    )
    (net (code "12") (name "/CPU_Reset") (class "Default")
      (node (ref "R14") (pin "2") (pinfunction "2_2") (pintype "passive"))
      (node (ref "R20") (pin "2") (pinfunction "2_2") (pintype "passive"))
    )
    (net (code "13") (name "/CPU_RnW") (class "Default")
      (node (ref "R10") (pin "2") (pinfunction "2_2") (pintype "passive"))
      (node (ref "R42") (pin "2") (pinfunction "2_2") (pintype "passive"))
    )
    (net (code "14") (name "/CPU_nInt") (class "Default")
      (node (ref "R43") (pin "2") (pinfunction "2_2") (pintype "passive"))
      (node (ref "R7") (pin "2") (pinfunction "2_2") (pintype "passive"))
    )
    (net (code "15") (name "/CS") (class "Default")
      (node (ref "R33") (pin "2") (pinfunction "2_2") (pintype "passive"))
      (node (ref "R67") (pin "1") (pinfunction "1_1") (pintype "passive"))
    )
    (net (code "16") (name "/GPIO_0") (class "Default")
      (node (ref "R60") (pin "2") (pinfunction "2_2") (pintype "passive"))
      (node (ref "R73") (pin "2") (pinfunction "2_2") (pintype "passive"))
    )
    (net (code "17") (name "/GPIO_1") (class "Default")
      (node (ref "R56") (pin "2") (pinfunction "2_2") (pintype "passive"))
      (node (ref "R70") (pin "2") (pinfunction "2_2") (pintype "passive"))
    )
    (net (code "18") (name "/MISO") (class "Default")
      (node (ref "R37") (pin "2") (pinfunction "2_2") (pintype "passive"))
      (node (ref "R57") (pin "1") (pinfunction "1_1") (pintype "passive"))
    )
    (net (code "19") (name "/MOSI") (class "Default")
      (node (ref "R39") (pin "2") (pinfunction "2_2") (pintype "passive"))
      (node (ref "R61") (pin "1") (pinfunction "1_1") (pintype "passive"))
    )
    (net (code "20") (name "/SCK") (class "Default")
      (node (ref "R35") (pin "2") (pinfunction "2_2") (pintype "passive"))
      (node (ref "R64") (pin "1") (pinfunction "1_1") (pintype "passive"))
    )
    (net (code "21") (name "/SCL") (class "Default")
      (node (ref "R40") (pin "1") (pinfunction "1_1") (pintype "passive"))
      (node (ref "R44") (pin "1") (pinfunction "1_1") (pintype "passive"))
      (node (ref "R49") (pin "1") (pinfunction "1_1") (pintype "passive"))
    )
    (net (code "22") (name "/SDA") (class "Default")
      (node (ref "R38") (pin "1") (pinfunction "1_1") (pintype "passive"))
      (node (ref "R45") (pin "1") (pinfunction "1_1") (pintype "passive"))
      (node (ref "R47") (pin "1") (pinfunction "1_1") (pintype "passive"))
    )
    (net (code "23") (name "/UART0_RX") (class "Default")
      (node (ref "M2") (pin "6") (pinfunction "LV4_6") (pintype "passive"))
      (node (ref "R68") (pin "2") (pinfunction "2_2") (pintype "passive"))
    )
    (net (code "24") (name "/UPDI") (class "Default")
      (node (ref "R18") (pin "2") (pinfunction "2_2") (pintype "passive"))
      (node (ref "R2") (pin "1") (pinfunction "1_1") (pintype "passive"))
    )
    (net (code "25") (name "/WiFi_Rst") (class "Default")
      (node (ref "R32") (pin "2") (pinfunction "2_2") (pintype "passive"))
      (node (ref "R74") (pin "1") (pinfunction "1_1") (pintype "passive"))
    )
    (net (code "26") (name "GND") (class "Default")
      (node (ref "C1") (pin "2") (pinfunction "2_2") (pintype "passive"))
      (node (ref "C2") (pin "2") (pinfunction "2_2") (pintype "passive"))
      (node (ref "C3") (pin "2") (pinfunction "2_2") (pintype "passive"))
      (node (ref "C4") (pin "2") (pinfunction "2_2") (pintype "passive"))
      (node (ref "C5") (pin "2") (pinfunction "2_2") (pintype "passive"))
      (node (ref "C6") (pin "2") (pinfunction "2_2") (pintype "passive"))
      (node (ref "C7") (pin "2") (pinfunction "2_2") (pintype "passive"))
      (node (ref "H1") (pin "13") (pinfunction "13_13") (pintype "passive"))
      (node (ref "H1") (pin "15") (pinfunction "15_15") (pintype "passive"))
      (node (ref "H2") (pin "6") (pinfunction "GND_6") (pintype "passive"))
      (node (ref "IC1") (pin "19") (pinfunction "GND_1_19") (pintype "passive"))
      (node (ref "IC1") (pin "29") (pinfunction "GND_2_29") (pintype "passive"))
      (node (ref "J1") (pin "11") (pinfunction "11_11") (pintype "passive"))
      (node (ref "J1") (pin "13") (pinfunction "13_13") (pintype "passive"))
      (node (ref "J1") (pin "15") (pinfunction "15_15") (pintype "passive"))
      (node (ref "J1") (pin "9") (pinfunction "9_9") (pintype "passive"))
      (node (ref "M1") (pin "4") (pinfunction "Gnd_4") (pintype "passive"))
      (node (ref "M1") (pin "9") (pinfunction "Gnd_9") (pintype "passive"))
      (node (ref "M2") (pin "4") (pinfunction "Gnd_4") (pintype "passive"))
      (node (ref "M2") (pin "9") (pinfunction "Gnd_9") (pintype "passive"))
      (node (ref "U1") (pin "18") (pinfunction "Gnd_18") (pintype "passive"))
      (node (ref "U1") (pin "19") (pinfunction "Gnd_19") (pintype "passive"))
    )
    (net (code "27") (name "Net-(H1-Pad2)") (class "Default")
      (node (ref "H1") (pin "2") (pinfunction "2_2") (pintype "passive"))
      (node (ref "R1") (pin "2") (pinfunction "2_2") (pintype "passive"))
    )
    (net (code "28") (name "Net-(H1-Pad4)") (class "Default")
      (node (ref "H1") (pin "4") (pinfunction "4_4") (pintype "passive"))
      (node (ref "R3") (pin "2") (pinfunction "2_2") (pintype "passive"))
    )
    (net (code "29") (name "Net-(H1-Pad5)") (class "Default")
      (node (ref "H1") (pin "5") (pinfunction "5_5") (pintype "passive"))
      (node (ref "R7") (pin "1") (pinfunction "1_1") (pintype "passive"))
    )
    (net (code "30") (name "Net-(H1-Pad6)") (class "Default")
      (node (ref "H1") (pin "6") (pinfunction "6_6") (pintype "passive"))
      (node (ref "R6") (pin "2") (pinfunction "2_2") (pintype "passive"))
    )
    (net (code "31") (name "Net-(H1-Pad7)") (class "Default")
      (node (ref "H1") (pin "7") (pinfunction "7_7") (pintype "passive"))
      (node (ref "R10") (pin "1") (pinfunction "1_1") (pintype "passive"))
    )
    (net (code "32") (name "Net-(H1-Pad8)") (class "Default")
      (node (ref "H1") (pin "8") (pinfunction "8_8") (pintype "passive"))
      (node (ref "R9") (pin "2") (pinfunction "2_2") (pintype "passive"))
    )
    (net (code "33") (name "Net-(H1-Pad9)") (class "Default")
      (node (ref "H1") (pin "9") (pinfunction "9_9") (pintype "passive"))
      (node (ref "R12") (pin "1") (pinfunction "1_1") (pintype "passive"))
    )
    (net (code "34") (name "Net-(H1-Pad10)") (class "Default")
      (node (ref "H1") (pin "10") (pinfunction "10_10") (pintype "passive"))
      (node (ref "R11") (pin "2") (pinfunction "2_2") (pintype "passive"))
    )
    (net (code "35") (name "Net-(H1-Pad11)") (class "Default")
      (node (ref "H1") (pin "11") (pinfunction "11_11") (pintype "passive"))
      (node (ref "R14") (pin "1") (pinfunction "1_1") (pintype "passive"))
    )
    (net (code "36") (name "Net-(H1-Pad12)") (class "Default")
      (node (ref "H1") (pin "12") (pinfunction "12_12") (pintype "passive"))
      (node (ref "R13") (pin "2") (pinfunction "2_2") (pintype "passive"))
    )
    (net (code "37") (name "Net-(H1-Pad14)") (class "Default")
      (node (ref "H1") (pin "14") (pinfunction "14_14") (pintype "passive"))
      (node (ref "R15") (pin "2") (pinfunction "2_2") (pintype "passive"))
    )
    (net (code "38") (name "Net-(H1-Pad16)") (class "Default")
      (node (ref "H1") (pin "16") (pinfunction "16_16") (pintype "passive"))
      (node (ref "R16") (pin "2") (pinfunction "2_2") (pintype "passive"))
    )
    (net (code "39") (name "Net-(H2-NC-Pad3)") (class "Default")
      (node (ref "H2") (pin "3") (pinfunction "NC_3") (pintype "passive"))
      (node (ref "R4") (pin "2") (pinfunction "2_2") (pintype "passive"))
    )
    (net (code "40") (name "Net-(H2-NC-Pad4)") (class "Default")
      (node (ref "H2") (pin "4") (pinfunction "NC_4") (pintype "passive"))
      (node (ref "R5") (pin "1") (pinfunction "1_1") (pintype "passive"))
    )
    (net (code "41") (name "Net-(H2-NC-Pad5)") (class "Default")
      (node (ref "H2") (pin "5") (pinfunction "NC_5") (pintype "passive"))
      (node (ref "R8") (pin "2") (pinfunction "2_2") (pintype "passive"))
    )
    (net (code "42") (name "Net-(H2-UDPI)") (class "Default")
      (node (ref "H2") (pin "1") (pinfunction "UDPI_1") (pintype "passive"))
      (node (ref "R2") (pin "2") (pinfunction "2_2") (pintype "passive"))
    )
    (net (code "43") (name "Net-(IC1-PA0)") (class "Default")
      (node (ref "IC1") (pin "30") (pinfunction "PA0_30") (pintype "passive"))
      (node (ref "R17") (pin "2") (pinfunction "2_2") (pintype "passive"))
    )
    (net (code "44") (name "Net-(IC1-PA1)") (class "Default")
      (node (ref "IC1") (pin "31") (pinfunction "PA1_31") (pintype "passive"))
      (node (ref "R19") (pin "2") (pinfunction "2_2") (pintype "passive"))
    )
    (net (code "45") (name "Net-(IC1-PA2)") (class "Default")
      (node (ref "IC1") (pin "32") (pinfunction "PA2_32") (pintype "passive"))
      (node (ref "R21") (pin "2") (pinfunction "2_2") (pintype "passive"))
    )
    (net (code "46") (name "Net-(IC1-PA3)") (class "Default")
      (node (ref "IC1") (pin "1") (pinfunction "PA3_1") (pintype "passive"))
      (node (ref "R23") (pin "2") (pinfunction "2_2") (pintype "passive"))
    )
    (net (code "47") (name "Net-(IC1-PA4)") (class "Default")
      (node (ref "IC1") (pin "2") (pinfunction "PA4_2") (pintype "passive"))
      (node (ref "R25") (pin "2") (pinfunction "2_2") (pintype "passive"))
    )
    (net (code "48") (name "Net-(IC1-PA5)") (class "Default")
      (node (ref "IC1") (pin "3") (pinfunction "PA5_3") (pintype "passive"))
      (node (ref "R27") (pin "2") (pinfunction "2_2") (pintype "passive"))
    )
    (net (code "49") (name "Net-(IC1-PA6)") (class "Default")
      (node (ref "IC1") (pin "4") (pinfunction "PA6_4") (pintype "passive"))
      (node (ref "R29") (pin "2") (pinfunction "2_2") (pintype "passive"))
    )
    (net (code "50") (name "Net-(IC1-PA7)") (class "Default")
      (node (ref "IC1") (pin "5") (pinfunction "PA7_5") (pintype "passive"))
      (node (ref "R31") (pin "2") (pinfunction "2_2") (pintype "passive"))
    )
    (net (code "51") (name "Net-(IC1-PC0)") (class "Default")
      (node (ref "IC1") (pin "6") (pinfunction "PC0_6") (pintype "passive"))
      (node (ref "R34") (pin "2") (pinfunction "2_2") (pintype "passive"))
    )
    (net (code "52") (name "Net-(IC1-PC1)") (class "Default")
      (node (ref "IC1") (pin "7") (pinfunction "PC1_7") (pintype "passive"))
      (node (ref "R36") (pin "2") (pinfunction "2_2") (pintype "passive"))
    )
    (net (code "53") (name "Net-(IC1-PC2)") (class "Default")
      (node (ref "IC1") (pin "8") (pinfunction "PC2_8") (pintype "passive"))
      (node (ref "R38") (pin "2") (pinfunction "2_2") (pintype "passive"))
    )
    (net (code "54") (name "Net-(IC1-PC3)") (class "Default")
      (node (ref "IC1") (pin "9") (pinfunction "PC3_9") (pintype "passive"))
      (node (ref "R40") (pin "2") (pinfunction "2_2") (pintype "passive"))
    )
    (net (code "55") (name "Net-(IC1-PD3)") (class "Default")
      (node (ref "IC1") (pin "13") (pinfunction "PD3_13") (pintype "passive"))
      (node (ref "R41") (pin "1") (pinfunction "1_1") (pintype "passive"))
    )
    (net (code "56") (name "Net-(IC1-PD4)") (class "Default")
      (node (ref "IC1") (pin "14") (pinfunction "PD4_14") (pintype "passive"))
      (node (ref "R39") (pin "1") (pinfunction "1_1") (pintype "passive"))
    )
    (net (code "57") (name "Net-(IC1-PD5)") (class "Default")
      (node (ref "IC1") (pin "15") (pinfunction "PD5_15") (pintype "passive"))
      (node (ref "R37") (pin "1") (pinfunction "1_1") (pintype "passive"))
    )
    (net (code "58") (name "Net-(IC1-PD6)") (class "Default")
      (node (ref "IC1") (pin "16") (pinfunction "PD6_16") (pintype "passive"))
      (node (ref "R35") (pin "1") (pinfunction "1_1") (pintype "passive"))
    )
    (net (code "59") (name "Net-(IC1-PD7)") (class "Default")
      (node (ref "IC1") (pin "17") (pinfunction "PD7_17") (pintype "passive"))
      (node (ref "R33") (pin "1") (pinfunction "1_1") (pintype "passive"))
    )
    (net (code "60") (name "Net-(IC1-PD~{1})") (class "Default")
      (node (ref "IC1") (pin "11") (pinfunction "PD~{1}_11") (pintype "passive"))
      (node (ref "R43") (pin "1") (pinfunction "1_1") (pintype "passive"))
    )
    (net (code "61") (name "Net-(IC1-PD~{2})") (class "Default")
      (node (ref "IC1") (pin "12") (pinfunction "PD~{2}_12") (pintype "passive"))
      (node (ref "R42") (pin "1") (pinfunction "1_1") (pintype "passive"))
    )
    (net (code "62") (name "Net-(IC1-PF0)") (class "Default")
      (node (ref "IC1") (pin "20") (pinfunction "PF0_20") (pintype "passive"))
      (node (ref "R32") (pin "1") (pinfunction "1_1") (pintype "passive"))
    )
    (net (code "63") (name "Net-(IC1-PF1)") (class "Default")
      (node (ref "IC1") (pin "21") (pinfunction "PF1_21") (pintype "passive"))
      (node (ref "R30") (pin "1") (pinfunction "1_1") (pintype "passive"))
    )
    (net (code "64") (name "Net-(IC1-PF2)") (class "Default")
      (node (ref "IC1") (pin "22") (pinfunction "PF2_22") (pintype "passive"))
      (node (ref "R28") (pin "1") (pinfunction "1_1") (pintype "passive"))
    )
    (net (code "65") (name "Net-(IC1-PF3)") (class "Default")
      (node (ref "IC1") (pin "23") (pinfunction "PF3_23") (pintype "passive"))
      (node (ref "R26") (pin "1") (pinfunction "1_1") (pintype "passive"))
    )
    (net (code "66") (name "Net-(IC1-PF4)") (class "Default")
      (node (ref "IC1") (pin "24") (pinfunction "PF4_24") (pintype "passive"))
      (node (ref "R24") (pin "1") (pinfunction "1_1") (pintype "passive"))
    )
    (net (code "67") (name "Net-(IC1-PF5)") (class "Default")
      (node (ref "IC1") (pin "25") (pinfunction "PF5_25") (pintype "passive"))
      (node (ref "R22") (pin "1") (pinfunction "1_1") (pintype "passive"))
    )
    (net (code "68") (name "Net-(IC1-PF6_(~{RESET)})") (class "Default")
      (node (ref "IC1") (pin "26") (pinfunction "PF6_(~{RESET)}_26") (pintype "passive"))
      (node (ref "R20") (pin "1") (pinfunction "1_1") (pintype "passive"))
    )
    (net (code "69") (name "Net-(IC1-PF7_(UPDI))") (class "Default")
      (node (ref "IC1") (pin "27") (pinfunction "PF7_(UPDI)_27") (pintype "passive"))
      (node (ref "R18") (pin "1") (pinfunction "1_1") (pintype "passive"))
    )
    (net (code "70") (name "Net-(J1-Pad2)") (class "Default")
      (node (ref "J1") (pin "2") (pinfunction "2_2") (pintype "passive"))
      (node (ref "R51") (pin "2") (pinfunction "2_2") (pintype "passive"))
    )
    (net (code "71") (name "Net-(J1-Pad4)") (class "Default")
      (node (ref "J1") (pin "4") (pinfunction "4_4") (pintype "passive"))
      (node (ref "R53") (pin "2") (pinfunction "2_2") (pintype "passive"))
    )
    (net (code "72") (name "Net-(J1-Pad5)") (class "Default")
      (node (ref "J1") (pin "5") (pinfunction "5_5") (pintype "passive"))
      (node (ref "R56") (pin "1") (pinfunction "1_1") (pintype "passive"))
    )
    (net (code "73") (name "Net-(J1-Pad6)") (class "Default")
      (node (ref "J1") (pin "6") (pinfunction "6_6") (pintype "passive"))
      (node (ref "R55") (pin "2") (pinfunction "2_2") (pintype "passive"))
    )
    (net (code "74") (name "Net-(J1-Pad7)") (class "Default")
      (node (ref "J1") (pin "7") (pinfunction "7_7") (pintype "passive"))
      (node (ref "R60") (pin "1") (pinfunction "1_1") (pintype "passive"))
    )
    (net (code "75") (name "Net-(J1-Pad8)") (class "Default")
      (node (ref "J1") (pin "8") (pinfunction "8_8") (pintype "passive"))
      (node (ref "R59") (pin "2") (pinfunction "2_2") (pintype "passive"))
    )
    (net (code "76") (name "Net-(J1-Pad10)") (class "Default")
      (node (ref "J1") (pin "10") (pinfunction "10_10") (pintype "passive"))
      (node (ref "R63") (pin "2") (pinfunction "2_2") (pintype "passive"))
    )
    (net (code "77") (name "Net-(J1-Pad12)") (class "Default")
      (node (ref "J1") (pin "12") (pinfunction "12_12") (pintype "passive"))
      (node (ref "R66") (pin "2") (pinfunction "2_2") (pintype "passive"))
    )
    (net (code "78") (name "Net-(J1-Pad14)") (class "Default")
      (node (ref "J1") (pin "14") (pinfunction "14_14") (pintype "passive"))
      (node (ref "R69") (pin "2") (pinfunction "2_2") (pintype "passive"))
    )
    (net (code "79") (name "Net-(J1-Pad16)") (class "Default")
      (node (ref "J1") (pin "16") (pinfunction "16_16") (pintype "passive"))
      (node (ref "R71") (pin "2") (pinfunction "2_2") (pintype "passive"))
    )
    (net (code "80") (name "Net-(LED1-A)") (class "Default")
      (node (ref "LED1") (pin "2") (pinfunction "A_2") (pintype "passive"))
      (node (ref "R46") (pin "1") (pinfunction "1_1") (pintype "passive"))
    )
    (net (code "81") (name "Net-(LED1-K)") (class "Default")
      (node (ref "LED1") (pin "1") (pinfunction "K_1") (pintype "passive"))
      (node (ref "R72") (pin "1") (pinfunction "1_1") (pintype "passive"))
    )
    (net (code "82") (name "Net-(M1-HV1)") (class "Default")
      (node (ref "M1") (pin "12") (pinfunction "HV1_12") (pintype "passive"))
      (node (ref "R51") (pin "1") (pinfunction "1_1") (pintype "passive"))
    )
    (net (code "83") (name "Net-(M1-HV2)") (class "Default")
      (node (ref "M1") (pin "11") (pinfunction "HV2_11") (pintype "passive"))
      (node (ref "R53") (pin "1") (pinfunction "1_1") (pintype "passive"))
    )
    (net (code "84") (name "Net-(M1-HV3)") (class "Default")
      (node (ref "M1") (pin "8") (pinfunction "HV3_8") (pintype "passive"))
      (node (ref "R55") (pin "1") (pinfunction "1_1") (pintype "passive"))
    )
    (net (code "85") (name "Net-(M1-HV4)") (class "Default")
      (node (ref "M1") (pin "7") (pinfunction "HV4_7") (pintype "passive"))
      (node (ref "R59") (pin "1") (pinfunction "1_1") (pintype "passive"))
    )
    (net (code "86") (name "Net-(M1-LV1)") (class "Default")
      (node (ref "M1") (pin "1") (pinfunction "LV1_1") (pintype "passive"))
      (node (ref "R48") (pin "2") (pinfunction "2_2") (pintype "passive"))
    )
    (net (code "87") (name "Net-(M1-LV2)") (class "Default")
      (node (ref "M1") (pin "2") (pinfunction "LV2_2") (pintype "passive"))
      (node (ref "R50") (pin "2") (pinfunction "2_2") (pintype "passive"))
    )
    (net (code "88") (name "Net-(M1-LV3)") (class "Default")
      (node (ref "M1") (pin "5") (pinfunction "LV3_5") (pintype "passive"))
      (node (ref "R52") (pin "2") (pinfunction "2_2") (pintype "passive"))
    )
    (net (code "89") (name "Net-(M1-LV4)") (class "Default")
      (node (ref "M1") (pin "6") (pinfunction "LV4_6") (pintype "passive"))
      (node (ref "R54") (pin "2") (pinfunction "2_2") (pintype "passive"))
    )
    (net (code "90") (name "Net-(M2-HV1)") (class "Default")
      (node (ref "M2") (pin "12") (pinfunction "HV1_12") (pintype "passive"))
      (node (ref "R63") (pin "1") (pinfunction "1_1") (pintype "passive"))
    )
    (net (code "91") (name "Net-(M2-HV2)") (class "Default")
      (node (ref "M2") (pin "11") (pinfunction "HV2_11") (pintype "passive"))
      (node (ref "R66") (pin "1") (pinfunction "1_1") (pintype "passive"))
    )
    (net (code "92") (name "Net-(M2-HV3)") (class "Default")
      (node (ref "M2") (pin "8") (pinfunction "HV3_8") (pintype "passive"))
      (node (ref "R69") (pin "1") (pinfunction "1_1") (pintype "passive"))
    )
    (net (code "93") (name "Net-(M2-HV4)") (class "Default")
      (node (ref "M2") (pin "7") (pinfunction "HV4_7") (pintype "passive"))
      (node (ref "R71") (pin "1") (pinfunction "1_1") (pintype "passive"))
    )
    (net (code "94") (name "Net-(M2-LV1)") (class "Default")
      (node (ref "M2") (pin "1") (pinfunction "LV1_1") (pintype "passive"))
      (node (ref "R58") (pin "2") (pinfunction "2_2") (pintype "passive"))
    )
    (net (code "95") (name "Net-(M2-LV2)") (class "Default")
      (node (ref "M2") (pin "2") (pinfunction "LV2_2") (pintype "passive"))
      (node (ref "R62") (pin "2") (pinfunction "2_2") (pintype "passive"))
    )
    (net (code "96") (name "Net-(M2-LV3)") (class "Default")
      (node (ref "M2") (pin "5") (pinfunction "LV3_5") (pintype "passive"))
      (node (ref "R65") (pin "2") (pinfunction "2_2") (pintype "passive"))
    )
    (net (code "97") (name "Net-(R4-Pad1)") (class "Default")
      (node (ref "R4") (pin "1") (pinfunction "1_1") (pintype "passive"))
      (node (ref "TP2") (pin "1") (pinfunction "1_1") (pintype "passive"))
    )
    (net (code "98") (name "Net-(R5-Pad2)") (class "Default")
      (node (ref "R5") (pin "2") (pinfunction "2_2") (pintype "passive"))
      (node (ref "TP3") (pin "1") (pinfunction "1_1") (pintype "passive"))
    )
    (net (code "99") (name "Net-(R8-Pad1)") (class "Default")
      (node (ref "R8") (pin "1") (pinfunction "1_1") (pintype "passive"))
      (node (ref "TP4") (pin "1") (pinfunction "1_1") (pintype "passive"))
    )
    (net (code "100") (name "Net-(R22-Pad2)") (class "Default")
      (node (ref "R22") (pin "2") (pinfunction "2_2") (pintype "passive"))
      (node (ref "TP5") (pin "1") (pinfunction "1_1") (pintype "passive"))
    )
    (net (code "101") (name "Net-(R24-Pad2)") (class "Default")
      (node (ref "R24") (pin "2") (pinfunction "2_2") (pintype "passive"))
      (node (ref "TP6") (pin "1") (pinfunction "1_1") (pintype "passive"))
    )
    (net (code "102") (name "Net-(R26-Pad2)") (class "Default")
      (node (ref "R26") (pin "2") (pinfunction "2_2") (pintype "passive"))
      (node (ref "TP7") (pin "1") (pinfunction "1_1") (pintype "passive"))
    )
    (net (code "103") (name "Net-(R28-Pad2)") (class "Default")
      (node (ref "R28") (pin "2") (pinfunction "2_2") (pintype "passive"))
      (node (ref "TP8") (pin "1") (pinfunction "1_1") (pintype "passive"))
    )
    (net (code "104") (name "Net-(R30-Pad2)") (class "Default")
      (node (ref "R30") (pin "2") (pinfunction "2_2") (pintype "passive"))
      (node (ref "TP9") (pin "1") (pinfunction "1_1") (pintype "passive"))
    )
    (net (code "105") (name "Net-(R34-Pad1)") (class "Default")
      (node (ref "R34") (pin "1") (pinfunction "1_1") (pintype "passive"))
      (node (ref "TP10") (pin "1") (pinfunction "1_1") (pintype "passive"))
    )
    (net (code "106") (name "Net-(R36-Pad1)") (class "Default")
      (node (ref "R36") (pin "1") (pinfunction "1_1") (pintype "passive"))
      (node (ref "TP11") (pin "1") (pinfunction "1_1") (pintype "passive"))
    )
    (net (code "107") (name "Net-(U1-Activity_LED)") (class "Default")
      (node (ref "R72") (pin "2") (pinfunction "2_2") (pintype "passive"))
      (node (ref "U1") (pin "28") (pinfunction "Activity_LED_28") (pintype "passive"))
    )
    (net (code "108") (name "Net-(U1-CS)") (class "Default")
      (node (ref "R67") (pin "2") (pinfunction "2_2") (pintype "passive"))
      (node (ref "U1") (pin "11") (pinfunction "CS_11") (pintype "passive"))
    )
    (net (code "109") (name "Net-(U1-GPIO_0)") (class "Default")
      (node (ref "R73") (pin "1") (pinfunction "1_1") (pintype "passive"))
      (node (ref "U1") (pin "10") (pinfunction "GPIO_0_10") (pintype "passive"))
    )
    (net (code "110") (name "Net-(U1-GPIO_1)") (class "Default")
      (node (ref "R70") (pin "1") (pinfunction "1_1") (pintype "passive"))
      (node (ref "U1") (pin "14") (pinfunction "GPIO_1_14") (pintype "passive"))
    )
    (net (code "111") (name "Net-(U1-GPIO_3)") (class "Default")
      (node (ref "R68") (pin "1") (pinfunction "1_1") (pintype "passive"))
      (node (ref "U1") (pin "13") (pinfunction "GPIO_3_13") (pintype "passive"))
    )
    (net (code "112") (name "Net-(U1-GPIO_5)") (class "Default")
      (node (ref "R65") (pin "1") (pinfunction "1_1") (pintype "passive"))
      (node (ref "U1") (pin "6") (pinfunction "GPIO_5_6") (pintype "passive"))
    )
    (net (code "113") (name "Net-(U1-GPIO_12)") (class "Default")
      (node (ref "R62") (pin "1") (pinfunction "1_1") (pintype "passive"))
      (node (ref "U1") (pin "24") (pinfunction "GPIO_12_24") (pintype "passive"))
    )
    (net (code "114") (name "Net-(U1-GPIO_13)") (class "Default")
      (node (ref "R58") (pin "1") (pinfunction "1_1") (pintype "passive"))
      (node (ref "U1") (pin "23") (pinfunction "GPIO_13_23") (pintype "passive"))
    )
    (net (code "115") (name "Net-(U1-GPIO_14)") (class "Default")
      (node (ref "R54") (pin "1") (pinfunction "1_1") (pintype "passive"))
      (node (ref "U1") (pin "25") (pinfunction "GPIO_14_25") (pintype "passive"))
    )
    (net (code "116") (name "Net-(U1-GPIO_17)") (class "Default")
      (node (ref "R52") (pin "1") (pinfunction "1_1") (pintype "passive"))
      (node (ref "U1") (pin "7") (pinfunction "GPIO_17_7") (pintype "passive"))
    )
    (net (code "117") (name "Net-(U1-GPIO_26)") (class "Default")
      (node (ref "R50") (pin "1") (pinfunction "1_1") (pintype "passive"))
      (node (ref "U1") (pin "27") (pinfunction "GPIO_26_27") (pintype "passive"))
    )
    (net (code "118") (name "Net-(U1-GPIO_27)") (class "Default")
      (node (ref "R48") (pin "1") (pinfunction "1_1") (pintype "passive"))
      (node (ref "U1") (pin "26") (pinfunction "GPIO_27_26") (pintype "passive"))
    )
    (net (code "119") (name "Net-(U1-MISO)") (class "Default")
      (node (ref "R57") (pin "2") (pinfunction "2_2") (pintype "passive"))
      (node (ref "U1") (pin "3") (pinfunction "MISO_3") (pintype "passive"))
    )
    (net (code "120") (name "Net-(U1-MOSI)") (class "Default")
      (node (ref "R61") (pin "2") (pinfunction "2_2") (pintype "passive"))
      (node (ref "U1") (pin "4") (pinfunction "MOSI_4") (pintype "passive"))
    )
    (net (code "121") (name "Net-(U1-RST)") (class "Default")
      (node (ref "R74") (pin "2") (pinfunction "2_2") (pintype "passive"))
      (node (ref "U1") (pin "22") (pinfunction "RST_22") (pintype "passive"))
    )
    (net (code "122") (name "Net-(U1-SCK)") (class "Default")
      (node (ref "R64") (pin "2") (pinfunction "2_2") (pintype "passive"))
      (node (ref "U1") (pin "5") (pinfunction "SCK_5") (pintype "passive"))
    )
    (net (code "123") (name "Net-(U1-SCL)") (class "Default")
      (node (ref "R49") (pin "2") (pinfunction "2_2") (pintype "passive"))
      (node (ref "U1") (pin "2") (pinfunction "SCL_2") (pintype "passive"))
    )
    (net (code "124") (name "Net-(U1-SDA)") (class "Default")
      (node (ref "R47") (pin "2") (pinfunction "2_2") (pintype "passive"))
      (node (ref "U1") (pin "1") (pinfunction "SDA_1") (pintype "passive"))
    )
    (net (code "125") (name "unconnected-(U1-NC-Pad8)") (class "Default")
      (node (ref "U1") (pin "8") (pinfunction "NC_8") (pintype "passive+no_connect"))
    )
    (net (code "126") (name "unconnected-(U1-NC-Pad9)") (class "Default")
      (node (ref "U1") (pin "9") (pinfunction "NC_9") (pintype "passive+no_connect"))
    )
    (net (code "127") (name "unconnected-(U1-NC-Pad12)") (class "Default")
      (node (ref "U1") (pin "12") (pinfunction "NC_12") (pintype "passive+no_connect"))
    )
    (net (code "128") (name "unconnected-(U1-NC-Pad15)") (class "Default")
      (node (ref "U1") (pin "15") (pinfunction "NC_15") (pintype "passive+no_connect"))
    )
    (net (code "129") (name "unconnected-(U1-NC-Pad21)") (class "Default")
      (node (ref "U1") (pin "21") (pinfunction "NC_21") (pintype "passive+no_connect"))
    )
    (net (code "130") (name "unconnected-(U1-NC-Pad29)") (class "Default")
      (node (ref "U1") (pin "29") (pinfunction "NC_29") (pintype "passive+no_connect"))
    )
    (net (code "131") (name "unconnected-(U1-NC-Pad30)") (class "Default")
      (node (ref "U1") (pin "30") (pinfunction "NC_30") (pintype "passive+no_connect"))
    )
    (net (code "132") (name "unconnected-(U1-NC-Pad31)") (class "Default")
      (node (ref "U1") (pin "31") (pinfunction "NC_31") (pintype "passive+no_connect"))
    )
    (net (code "133") (name "unconnected-(U1-NC-Pad32)") (class "Default")
      (node (ref "U1") (pin "32") (pinfunction "NC_32") (pintype "passive+no_connect"))
    )
    (net (code "134") (name "unconnected-(U1-NC-Pad33)") (class "Default")
      (node (ref "U1") (pin "33") (pinfunction "NC_33") (pintype "passive+no_connect"))
    )
    (net (code "135") (name "unconnected-(U1-NC-Pad34)") (class "Default")
      (node (ref "U1") (pin "34") (pinfunction "NC_34") (pintype "passive+no_connect"))
    )
    (net (code "136") (name "unconnected-(U1-NC-Pad35)") (class "Default")
      (node (ref "U1") (pin "35") (pinfunction "NC_35") (pintype "passive+no_connect"))
    )
    (net (code "137") (name "unconnected-(U1-NC-Pad36)") (class "Default")
      (node (ref "U1") (pin "36") (pinfunction "NC_36") (pintype "passive+no_connect"))
    )
  )
)
